# LM399_reference_board.net
KiCad netlist of a schematic drawn in EAGLE
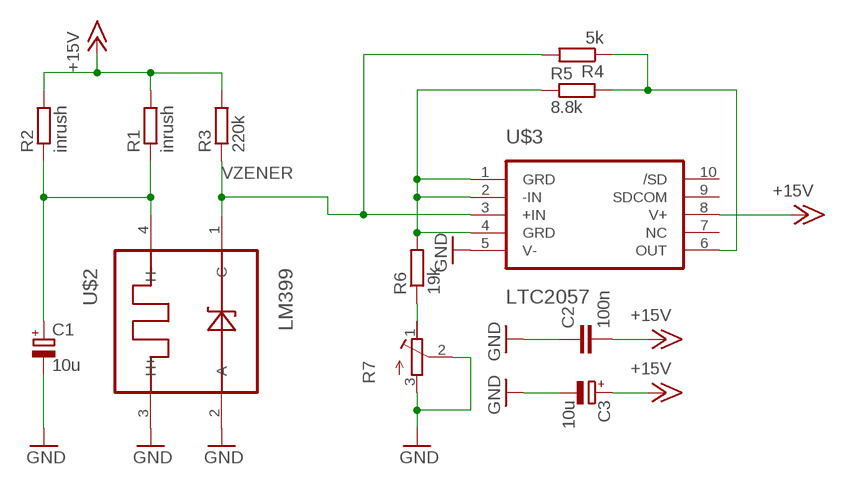
[diagram p0: schematic, sheet 1]

(export (version "E")
  (design (tool "Eeschema 10.0.6"))
  (components
    (comp (ref "C1")
      (value "10u")
      (footprint "eagle-import:SMC_D")
      (libsource (lib "eagle-import") (part "CPOL-EUSMCD"))
    )
    (comp (ref "C2")
      (value "100n")
      (footprint "eagle-import:C0603")
      (libsource (lib "eagle-import") (part "C-EUC0603"))
    )
    (comp (ref "C3")
      (value "10u")
      (footprint "eagle-import:SMC_D")
      (libsource (lib "eagle-import") (part "CPOL-EUSMCD"))
    )
    (comp (ref "R1")
      (value "inrush")
      (footprint "eagle-import:R1206")
      (libsource (lib "eagle-import") (part "R-EU_R1206"))
    )
    (comp (ref "R2")
      (value "inrush")
      (footprint "eagle-import:0309_12")
      (libsource (lib "eagle-import") (part "R-EU_0309/12"))
    )
    (comp (ref "R3")
      (value "220k")
      (footprint "eagle-import:0207_10")
      (libsource (lib "eagle-import") (part "R-EU_0207/10"))
    )
    (comp (ref "R4")
      (value "5k")
      (footprint "eagle-import:0207_10")
      (libsource (lib "eagle-import") (part "R-EU_0207/10"))
    )
    (comp (ref "R5")
      (value "8.8k")
      (footprint "eagle-import:0207_10")
      (libsource (lib "eagle-import") (part "R-EU_0207/10"))
    )
    (comp (ref "R6")
      (value "19k")
      (footprint "eagle-import:0207_10")
      (libsource (lib "eagle-import") (part "R-EU_0207/10"))
    )
    (comp (ref "R7")
      (value "R-TRIMMT93YA")
      (footprint "eagle-import:RTRIMT93YA")
      (libsource (lib "eagle-import") (part "R-TRIMMT93YA"))
    )
    (comp (ref "U$2")
      (value "LM399")
      (footprint "eagle-import:H4-TO46-4PIN")
      (libsource (lib "eagle-import") (part "LM399"))
    )
    (comp (ref "U$3")
      (value "LTC2057")
      (footprint "eagle-import:MS-MSOP10")
      (libsource (lib "eagle-import") (part "LTC2057"))
    )
  )
  (nets
    (net (code "1") (name "+15V") (class "Default")
      (node (ref "C2") (pin "2") (pinfunction "2_2") (pintype "passive"))
      (node (ref "C3") (pin "+") (pinfunction "+_+") (pintype "passive"))
      (node (ref "R1") (pin "2") (pinfunction "2_2") (pintype "passive"))
      (node (ref "R2") (pin "2") (pinfunction "2_2") (pintype "passive"))
      (node (ref "R3") (pin "2") (pinfunction "2_2") (pintype "passive"))
      (node (ref "U$3") (pin "8") (pinfunction "V+_8") (pintype "bidirectional"))
    )
    (net (code "2") (name "/VZENER") (class "Default")
      (node (ref "R3") (pin "1") (pinfunction "1_1") (pintype "passive"))
      (node (ref "R4") (pin "2") (pinfunction "2_2") (pintype "passive"))
      (node (ref "U$2") (pin "1") (pinfunction "C_1") (pintype "input"))
      (node (ref "U$3") (pin "3") (pinfunction "+IN_3") (pintype "bidirectional"))
    )
    (net (code "3") (name "GND") (class "Default")
      (node (ref "C1") (pin "-") (pinfunction "-_-") (pintype "passive"))
      (node (ref "C2") (pin "1") (pinfunction "1_1") (pintype "passive"))
      (node (ref "C3") (pin "-") (pinfunction "-_-") (pintype "passive"))
      (node (ref "R7") (pin "2") (pinfunction "S_2") (pintype "passive"))
      (node (ref "R7") (pin "3") (pinfunction "E_3") (pintype "passive"))
      (node (ref "U$2") (pin "2") (pinfunction "A_2") (pintype "input"))
      (node (ref "U$2") (pin "3") (pinfunction "H+_3") (pintype "input"))
      (node (ref "U$3") (pin "5") (pinfunction "V-_5") (pintype "bidirectional"))
    )
    (net (code "4") (name "Net-(R7-A)") (class "Default")
      (node (ref "R6") (pin "1") (pinfunction "1_1") (pintype "passive"))
      (node (ref "R7") (pin "1") (pinfunction "A_1") (pintype "passive"))
    )
    (net (code "5") (name "Net-(U$2-H-)") (class "Default")
      (node (ref "C1") (pin "+") (pinfunction "+_+") (pintype "passive"))
      (node (ref "R1") (pin "1") (pinfunction "1_1") (pintype "passive"))
      (node (ref "R2") (pin "1") (pinfunction "1_1") (pintype "passive"))
      (node (ref "U$2") (pin "4") (pinfunction "H-_4") (pintype "input"))
    )
    (net (code "6") (name "Net-(U$3--IN)") (class "Default")
      (node (ref "R5") (pin "1") (pinfunction "1_1") (pintype "passive"))
      (node (ref "R6") (pin "2") (pinfunction "2_2") (pintype "passive"))
      (node (ref "U$3") (pin "1") (pinfunction "GRD_1") (pintype "bidirectional"))
      (node (ref "U$3") (pin "2") (pinfunction "-IN_2") (pintype "bidirectional"))
      (node (ref "U$3") (pin "4") (pinfunction "GRD_4") (pintype "bidirectional"))
    )
    (net (code "7") (name "Net-(U$3-OUT)") (class "Default")
      (node (ref "R4") (pin "1") (pinfunction "1_1") (pintype "passive"))
      (node (ref "R5") (pin "2") (pinfunction "2_2") (pintype "passive"))
      (node (ref "U$3") (pin "6") (pinfunction "OUT_6") (pintype "bidirectional"))
    )
    (net (code "8") (name "unconnected-(U$3-NC-Pad7)") (class "Default")
      (node (ref "U$3") (pin "7") (pinfunction "NC_7") (pintype "bidirectional"))
    )
    (net (code "9") (name "unconnected-(U$3-SDCOM-Pad9)") (class "Default")
      (node (ref "U$3") (pin "9") (pinfunction "SDCOM_9") (pintype "bidirectional"))
    )
    (net (code "10") (name "unconnected-(U$3-{slash}SD-Pad10)") (class "Default")
      (node (ref "U$3") (pin "10") (pinfunction "/SD_10") (pintype "bidirectional"))
    )
  )
)
